# processor_beaglebone.net
KiCad netlist of a schematic drawn in Altium Designer
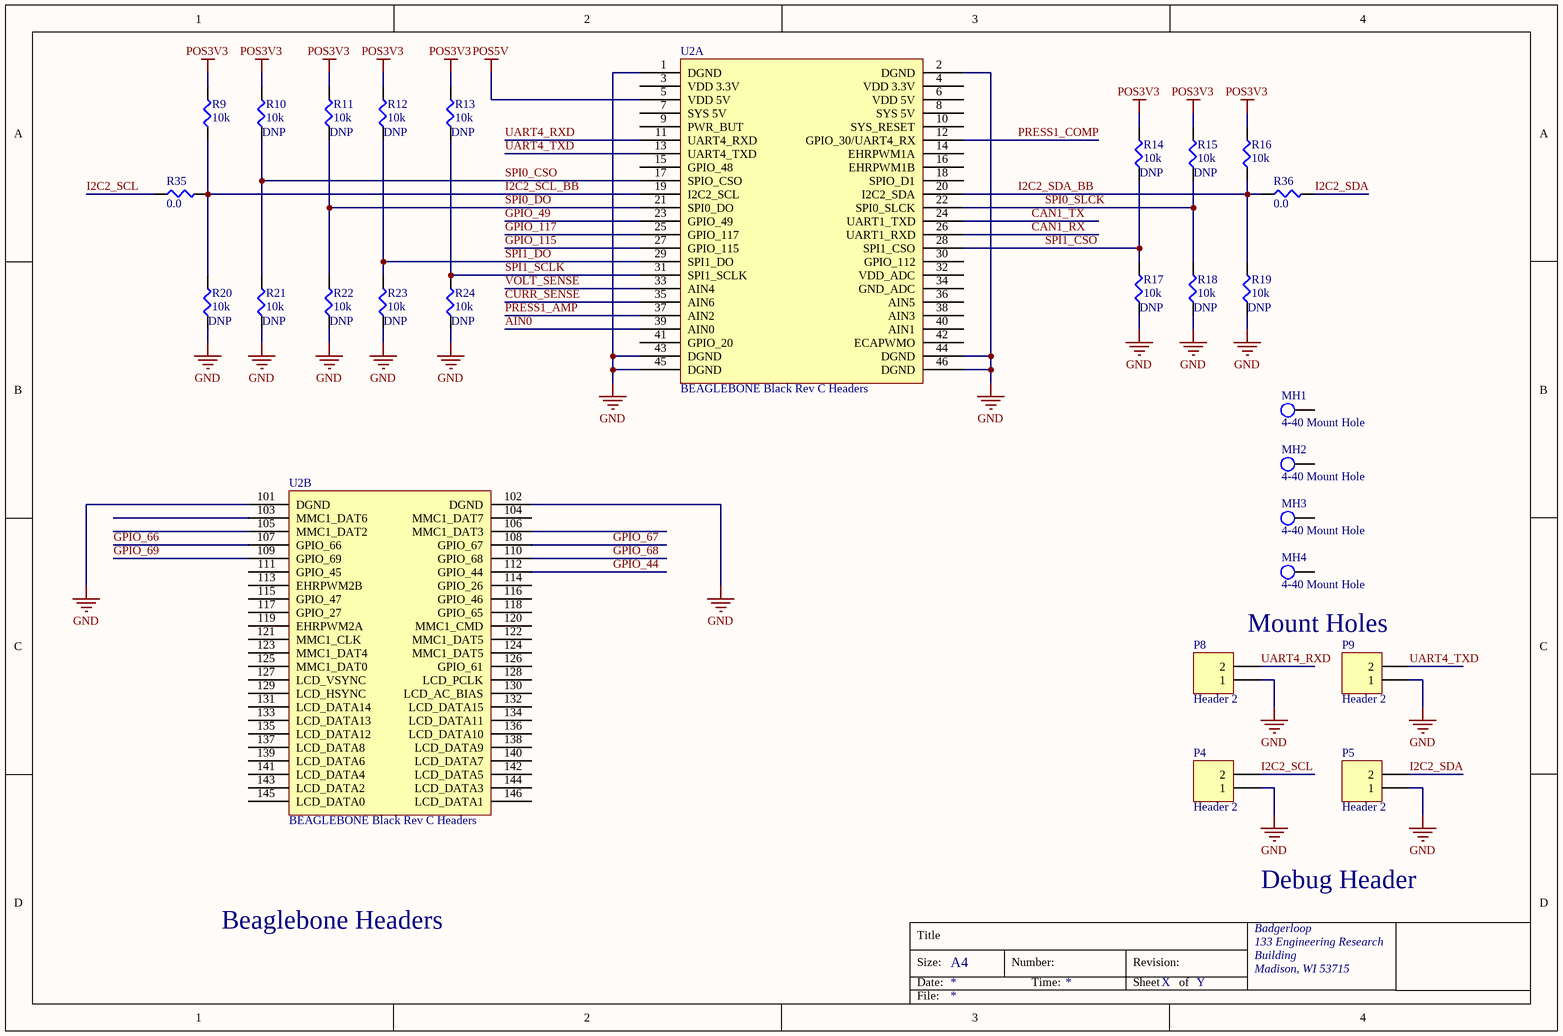
[diagram p0: processor_beaglebone.SchDoc]

(export (version "E")
  (design (tool "Eeschema 10.0.6"))
  (components
    (comp (ref "MH1")
      (value "4-40 Mount Hole")
      (footprint "MH")
      (libsource (lib "misc") (part "4-40 Mount Hole"))
    )
    (comp (ref "MH2")
      (value "4-40 Mount Hole")
      (footprint "MH")
      (libsource (lib "misc") (part "4-40 Mount Hole"))
    )
    (comp (ref "MH3")
      (value "4-40 Mount Hole")
      (footprint "MH")
      (libsource (lib "misc") (part "4-40 Mount Hole"))
    )
    (comp (ref "MH4")
      (value "4-40 Mount Hole")
      (footprint "MH")
      (libsource (lib "misc") (part "4-40 Mount Hole"))
    )
    (comp (ref "P4")
      (value "Header 2")
      (footprint "Pin Header 1x2 TH Pitch 2.54mm")
      (description "Header, 2-Pin")
      (fields (field (name "PUBLISHER") "Altium Limited"))
      (libsource (lib "connector") (part "Header 2"))
    )
    (comp (ref "P5")
      (value "Header 2")
      (footprint "Pin Header 1x2 TH Pitch 2.54mm")
      (description "Header, 2-Pin")
      (fields (field (name "PUBLISHER") "Altium Limited"))
      (libsource (lib "connector") (part "Header 2"))
    )
    (comp (ref "P8")
      (value "Header 2")
      (footprint "Pin Header 1x2 TH Pitch 2.54mm")
      (description "Header, 2-Pin")
      (fields (field (name "PUBLISHER") "Altium Limited"))
      (libsource (lib "connector") (part "Header 2"))
    )
    (comp (ref "P9")
      (value "Header 2")
      (footprint "Pin Header 1x2 TH Pitch 2.54mm")
      (description "Header, 2-Pin")
      (fields (field (name "PUBLISHER") "Altium Limited"))
      (libsource (lib "connector") (part "Header 2"))
    )
    (comp (ref "R9")
      (value "10k")
      (footprint "SMD-0402-RES")
      (description "RES SMD 10K OHM 5% 1/10W 0402")
      (fields (field (name "PART NUMBER") "ERJ-2GEJ103X") (field (name "DIGI-KEY PART NUMBER") "P10KJCT-ND"))
      (libsource (lib "resistor") (part "ERJ-2GEJ103X"))
    )
    (comp (ref "R10")
      (value "10k")
      (footprint "SMD-0402-RES")
      (description "RES SMD 10K OHM 5% 1/10W 0402")
      (fields
        (field (name "PART NUMBER") "ERJ-2GEJ103X")
        (field (name "DIGI-KEY PART NUMBER") "P10KJCT-ND")
        (field (name "DNP") "DNP")
      )
      (libsource (lib "resistor") (part "ERJ-2GEJ103X"))
    )
    (comp (ref "R11")
      (value "10k")
      (footprint "SMD-0402-RES")
      (description "RES SMD 10K OHM 5% 1/10W 0402")
      (fields
        (field (name "PART NUMBER") "ERJ-2GEJ103X")
        (field (name "DIGI-KEY PART NUMBER") "P10KJCT-ND")
        (field (name "DNP") "DNP")
      )
      (libsource (lib "resistor") (part "ERJ-2GEJ103X"))
    )
    (comp (ref "R12")
      (value "10k")
      (footprint "SMD-0402-RES")
      (description "RES SMD 10K OHM 5% 1/10W 0402")
      (fields
        (field (name "PART NUMBER") "ERJ-2GEJ103X")
        (field (name "DIGI-KEY PART NUMBER") "P10KJCT-ND")
        (field (name "DNP") "DNP")
      )
      (libsource (lib "resistor") (part "ERJ-2GEJ103X"))
    )
    (comp (ref "R13")
      (value "10k")
      (footprint "SMD-0402-RES")
      (description "RES SMD 10K OHM 5% 1/10W 0402")
      (fields
        (field (name "PART NUMBER") "ERJ-2GEJ103X")
        (field (name "DIGI-KEY PART NUMBER") "P10KJCT-ND")
        (field (name "DNP") "DNP")
      )
      (libsource (lib "resistor") (part "ERJ-2GEJ103X"))
    )
    (comp (ref "R14")
      (value "10k")
      (footprint "SMD-0402-RES")
      (description "RES SMD 10K OHM 5% 1/10W 0402")
      (fields
        (field (name "PART NUMBER") "ERJ-2GEJ103X")
        (field (name "DIGI-KEY PART NUMBER") "P10KJCT-ND")
        (field (name "DNP") "DNP")
      )
      (libsource (lib "resistor") (part "ERJ-2GEJ103X"))
    )
    (comp (ref "R15")
      (value "10k")
      (footprint "SMD-0402-RES")
      (description "RES SMD 10K OHM 5% 1/10W 0402")
      (fields
        (field (name "PART NUMBER") "ERJ-2GEJ103X")
        (field (name "DIGI-KEY PART NUMBER") "P10KJCT-ND")
        (field (name "DNP") "DNP")
      )
      (libsource (lib "resistor") (part "ERJ-2GEJ103X"))
    )
    (comp (ref "R16")
      (value "10k")
      (footprint "SMD-0402-RES")
      (description "RES SMD 10K OHM 5% 1/10W 0402")
      (fields (field (name "PART NUMBER") "ERJ-2GEJ103X") (field (name "DIGI-KEY PART NUMBER") "P10KJCT-ND"))
      (libsource (lib "resistor") (part "ERJ-2GEJ103X"))
    )
    (comp (ref "R17")
      (value "10k")
      (footprint "SMD-0402-RES")
      (description "RES SMD 10K OHM 5% 1/10W 0402")
      (fields
        (field (name "PART NUMBER") "ERJ-2GEJ103X")
        (field (name "DIGI-KEY PART NUMBER") "P10KJCT-ND")
        (field (name "DNP") "DNP")
      )
      (libsource (lib "resistor") (part "ERJ-2GEJ103X"))
    )
    (comp (ref "R18")
      (value "10k")
      (footprint "SMD-0402-RES")
      (description "RES SMD 10K OHM 5% 1/10W 0402")
      (fields
        (field (name "PART NUMBER") "ERJ-2GEJ103X")
        (field (name "DIGI-KEY PART NUMBER") "P10KJCT-ND")
        (field (name "DNP") "DNP")
      )
      (libsource (lib "resistor") (part "ERJ-2GEJ103X"))
    )
    (comp (ref "R19")
      (value "10k")
      (footprint "SMD-0402-RES")
      (description "RES SMD 10K OHM 5% 1/10W 0402")
      (fields
        (field (name "PART NUMBER") "ERJ-2GEJ103X")
        (field (name "DIGI-KEY PART NUMBER") "P10KJCT-ND")
        (field (name "DNP") "DNP")
      )
      (libsource (lib "resistor") (part "ERJ-2GEJ103X"))
    )
    (comp (ref "R20")
      (value "10k")
      (footprint "SMD-0402-RES")
      (description "RES SMD 10K OHM 5% 1/10W 0402")
      (fields
        (field (name "PART NUMBER") "ERJ-2GEJ103X")
        (field (name "DIGI-KEY PART NUMBER") "P10KJCT-ND")
        (field (name "DNP") "DNP")
      )
      (libsource (lib "resistor") (part "ERJ-2GEJ103X"))
    )
    (comp (ref "R21")
      (value "10k")
      (footprint "SMD-0402-RES")
      (description "RES SMD 10K OHM 5% 1/10W 0402")
      (fields
        (field (name "PART NUMBER") "ERJ-2GEJ103X")
        (field (name "DIGI-KEY PART NUMBER") "P10KJCT-ND")
        (field (name "DNP") "DNP")
      )
      (libsource (lib "resistor") (part "ERJ-2GEJ103X"))
    )
    (comp (ref "R22")
      (value "10k")
      (footprint "SMD-0402-RES")
      (description "RES SMD 10K OHM 5% 1/10W 0402")
      (fields
        (field (name "PART NUMBER") "ERJ-2GEJ103X")
        (field (name "DIGI-KEY PART NUMBER") "P10KJCT-ND")
        (field (name "DNP") "DNP")
      )
      (libsource (lib "resistor") (part "ERJ-2GEJ103X"))
    )
    (comp (ref "R23")
      (value "10k")
      (footprint "SMD-0402-RES")
      (description "RES SMD 10K OHM 5% 1/10W 0402")
      (fields
        (field (name "PART NUMBER") "ERJ-2GEJ103X")
        (field (name "DIGI-KEY PART NUMBER") "P10KJCT-ND")
        (field (name "DNP") "DNP")
      )
      (libsource (lib "resistor") (part "ERJ-2GEJ103X"))
    )
    (comp (ref "R24")
      (value "10k")
      (footprint "SMD-0402-RES")
      (description "RES SMD 10K OHM 5% 1/10W 0402")
      (fields
        (field (name "PART NUMBER") "ERJ-2GEJ103X")
        (field (name "DIGI-KEY PART NUMBER") "P10KJCT-ND")
        (field (name "DNP") "DNP")
      )
      (libsource (lib "resistor") (part "ERJ-2GEJ103X"))
    )
    (comp (ref "R35")
      (value "0.0")
      (footprint "SMD-0402-RES")
      (description "RES SMD 0.0OHM JUMPER 1/10W 0402")
      (fields (field (name "PART NUMBER") "ERJ-2GE0R00X") (field (name "DIGI-KEY PART NUMBER") "P0.0JCT-ND"))
      (libsource (lib "resistor") (part "ERJ-2GE0R00X"))
    )
    (comp (ref "R36")
      (value "0.0")
      (footprint "SMD-0402-RES")
      (description "RES SMD 0.0OHM JUMPER 1/10W 0402")
      (fields (field (name "PART NUMBER") "ERJ-2GE0R00X") (field (name "DIGI-KEY PART NUMBER") "P0.0JCT-ND"))
      (libsource (lib "resistor") (part "ERJ-2GE0R00X"))
    )
    (comp (ref "U2")
      (value "BEAGLEBONE Black Rev C Headers")
      (footprint "Beaglebone_Topside")
      (description "Beaglebone Black Rev C Header")
      (libsource (lib "temp") (part "Beaglebone"))
    )
  )
  (nets
    (net (code "1") (name "/AIN0") (class "Default")
      (node (ref "U2") (pin "39") (pinfunction "AIN0_39") (pintype "passive"))
    )
    (net (code "2") (name "/CAN1_RX") (class "Default")
      (node (ref "U2") (pin "26") (pinfunction "UART1_RXD_26") (pintype "passive"))
    )
    (net (code "3") (name "/CAN1_TX") (class "Default")
      (node (ref "U2") (pin "24") (pinfunction "UART1_TXD_24") (pintype "passive"))
    )
    (net (code "4") (name "/CURR_SENSE") (class "Default")
      (node (ref "U2") (pin "35") (pinfunction "AIN6_35") (pintype "passive"))
    )
    (net (code "5") (name "/GPIO_44") (class "Default")
      (node (ref "U2") (pin "112") (pinfunction "GPIO_44_112") (pintype "passive"))
    )
    (net (code "6") (name "/GPIO_49") (class "Default")
      (node (ref "U2") (pin "23") (pinfunction "GPIO_49_23") (pintype "passive"))
    )
    (net (code "7") (name "/GPIO_66") (class "Default")
      (node (ref "U2") (pin "107") (pinfunction "GPIO_66_107") (pintype "passive"))
    )
    (net (code "8") (name "/GPIO_67") (class "Default")
      (node (ref "U2") (pin "108") (pinfunction "GPIO_67_108") (pintype "passive"))
    )
    (net (code "9") (name "/GPIO_68") (class "Default")
      (node (ref "U2") (pin "110") (pinfunction "GPIO_68_110") (pintype "passive"))
    )
    (net (code "10") (name "/GPIO_69") (class "Default")
      (node (ref "U2") (pin "109") (pinfunction "GPIO_69_109") (pintype "passive"))
    )
    (net (code "11") (name "/GPIO_115") (class "Default")
      (node (ref "U2") (pin "27") (pinfunction "GPIO_115_27") (pintype "passive"))
    )
    (net (code "12") (name "/GPIO_117") (class "Default")
      (node (ref "U2") (pin "25") (pinfunction "GPIO_117_25") (pintype "passive"))
    )
    (net (code "13") (name "/I2C2_SCL") (class "Default")
      (node (ref "P4") (pin "2") (pinfunction "2_2") (pintype "passive"))
      (node (ref "R35") (pin "1") (pinfunction "1_1") (pintype "passive"))
    )
    (net (code "14") (name "/I2C2_SCL_BB") (class "Default")
      (node (ref "R20") (pin "2") (pinfunction "2_2") (pintype "passive"))
      (node (ref "R35") (pin "2") (pinfunction "2_2") (pintype "passive"))
      (node (ref "R9") (pin "1") (pinfunction "1_1") (pintype "passive"))
      (node (ref "U2") (pin "19") (pinfunction "I2C2_SCL_19") (pintype "passive"))
    )
    (net (code "15") (name "/I2C2_SDA") (class "Default")
      (node (ref "P5") (pin "2") (pinfunction "2_2") (pintype "passive"))
      (node (ref "R36") (pin "2") (pinfunction "2_2") (pintype "passive"))
    )
    (net (code "16") (name "/I2C2_SDA_BB") (class "Default")
      (node (ref "R16") (pin "1") (pinfunction "1_1") (pintype "passive"))
      (node (ref "R19") (pin "2") (pinfunction "2_2") (pintype "passive"))
      (node (ref "R36") (pin "1") (pinfunction "1_1") (pintype "passive"))
      (node (ref "U2") (pin "20") (pinfunction "I2C2_SDA_20") (pintype "passive"))
    )
    (net (code "17") (name "/PRESS1_AMP") (class "Default")
      (node (ref "U2") (pin "37") (pinfunction "AIN2_37") (pintype "passive"))
    )
    (net (code "18") (name "/PRESS1_COMP") (class "Default")
      (node (ref "U2") (pin "12") (pinfunction "GPIO_30/UART4_RX_12") (pintype "passive"))
    )
    (net (code "19") (name "/SPI0_CSO") (class "Default")
      (node (ref "R10") (pin "1") (pinfunction "1_1") (pintype "passive"))
      (node (ref "R21") (pin "2") (pinfunction "2_2") (pintype "passive"))
      (node (ref "U2") (pin "17") (pinfunction "SPIO_CSO_17") (pintype "passive"))
    )
    (net (code "20") (name "/SPI0_DO") (class "Default")
      (node (ref "R11") (pin "1") (pinfunction "1_1") (pintype "passive"))
      (node (ref "R22") (pin "2") (pinfunction "2_2") (pintype "passive"))
      (node (ref "U2") (pin "21") (pinfunction "SPI0_DO_21") (pintype "passive"))
    )
    (net (code "21") (name "/SPI0_SLCK") (class "Default")
      (node (ref "R15") (pin "1") (pinfunction "1_1") (pintype "passive"))
      (node (ref "R18") (pin "2") (pinfunction "2_2") (pintype "passive"))
      (node (ref "U2") (pin "22") (pinfunction "SPI0_SLCK_22") (pintype "passive"))
    )
    (net (code "22") (name "/SPI1_CSO") (class "Default")
      (node (ref "R14") (pin "1") (pinfunction "1_1") (pintype "passive"))
      (node (ref "R17") (pin "2") (pinfunction "2_2") (pintype "passive"))
      (node (ref "U2") (pin "28") (pinfunction "SPI1_CSO_28") (pintype "passive"))
    )
    (net (code "23") (name "/SPI1_DO") (class "Default")
      (node (ref "R12") (pin "1") (pinfunction "1_1") (pintype "passive"))
      (node (ref "R23") (pin "2") (pinfunction "2_2") (pintype "passive"))
      (node (ref "U2") (pin "29") (pinfunction "SPI1_DO_29") (pintype "passive"))
    )
    (net (code "24") (name "/SPI1_SCLK") (class "Default")
      (node (ref "R13") (pin "1") (pinfunction "1_1") (pintype "passive"))
      (node (ref "R24") (pin "2") (pinfunction "2_2") (pintype "passive"))
      (node (ref "U2") (pin "31") (pinfunction "SPI1_SCLK_31") (pintype "passive"))
    )
    (net (code "25") (name "/UART4_RXD") (class "Default")
      (node (ref "P8") (pin "2") (pinfunction "2_2") (pintype "passive"))
      (node (ref "U2") (pin "11") (pinfunction "UART4_RXD_11") (pintype "passive"))
    )
    (net (code "26") (name "/UART4_TXD") (class "Default")
      (node (ref "P9") (pin "2") (pinfunction "2_2") (pintype "passive"))
      (node (ref "U2") (pin "13") (pinfunction "UART4_TXD_13") (pintype "passive"))
    )
    (net (code "27") (name "/VOLT_SENSE") (class "Default")
      (node (ref "U2") (pin "33") (pinfunction "AIN4_33") (pintype "passive"))
    )
    (net (code "28") (name "GND") (class "Default")
      (node (ref "P4") (pin "1") (pinfunction "1_1") (pintype "passive"))
      (node (ref "P5") (pin "1") (pinfunction "1_1") (pintype "passive"))
      (node (ref "P8") (pin "1") (pinfunction "1_1") (pintype "passive"))
      (node (ref "P9") (pin "1") (pinfunction "1_1") (pintype "passive"))
      (node (ref "R17") (pin "1") (pinfunction "1_1") (pintype "passive"))
      (node (ref "R18") (pin "1") (pinfunction "1_1") (pintype "passive"))
      (node (ref "R19") (pin "1") (pinfunction "1_1") (pintype "passive"))
      (node (ref "R20") (pin "1") (pinfunction "1_1") (pintype "passive"))
      (node (ref "R21") (pin "1") (pinfunction "1_1") (pintype "passive"))
      (node (ref "R22") (pin "1") (pinfunction "1_1") (pintype "passive"))
      (node (ref "R23") (pin "1") (pinfunction "1_1") (pintype "passive"))
      (node (ref "R24") (pin "1") (pinfunction "1_1") (pintype "passive"))
      (node (ref "U2") (pin "1") (pinfunction "DGND_1") (pintype "passive"))
      (node (ref "U2") (pin "101") (pinfunction "DGND_101") (pintype "passive"))
      (node (ref "U2") (pin "102") (pinfunction "DGND_102") (pintype "passive"))
      (node (ref "U2") (pin "2") (pinfunction "DGND_2") (pintype "passive"))
      (node (ref "U2") (pin "43") (pinfunction "DGND_43") (pintype "passive"))
      (node (ref "U2") (pin "44") (pinfunction "DGND_44") (pintype "passive"))
      (node (ref "U2") (pin "45") (pinfunction "DGND_45") (pintype "passive"))
      (node (ref "U2") (pin "46") (pinfunction "DGND_46") (pintype "passive"))
    )
    (net (code "29") (name "POS3V3") (class "Default")
      (node (ref "R10") (pin "2") (pinfunction "2_2") (pintype "passive"))
      (node (ref "R11") (pin "2") (pinfunction "2_2") (pintype "passive"))
      (node (ref "R12") (pin "2") (pinfunction "2_2") (pintype "passive"))
      (node (ref "R13") (pin "2") (pinfunction "2_2") (pintype "passive"))
      (node (ref "R14") (pin "2") (pinfunction "2_2") (pintype "passive"))
      (node (ref "R15") (pin "2") (pinfunction "2_2") (pintype "passive"))
      (node (ref "R16") (pin "2") (pinfunction "2_2") (pintype "passive"))
      (node (ref "R9") (pin "2") (pinfunction "2_2") (pintype "passive"))
    )
    (net (code "30") (name "POS5V") (class "Default")
      (node (ref "U2") (pin "5") (pinfunction "VDD_5V_5") (pintype "passive"))
    )
    (net (code "31") (name "unconnected-(MH1-Pad46)") (class "Default")
      (node (ref "MH1") (pin "46") (pinfunction "46_46") (pintype "passive"))
    )
    (net (code "32") (name "unconnected-(MH2-Pad46)") (class "Default")
      (node (ref "MH2") (pin "46") (pinfunction "46_46") (pintype "passive"))
    )
    (net (code "33") (name "unconnected-(MH3-Pad46)") (class "Default")
      (node (ref "MH3") (pin "46") (pinfunction "46_46") (pintype "passive"))
    )
    (net (code "34") (name "unconnected-(MH4-Pad46)") (class "Default")
      (node (ref "MH4") (pin "46") (pinfunction "46_46") (pintype "passive"))
    )
    (net (code "35") (name "unconnected-(U2A-AIN1-Pad40)") (class "Default")
      (node (ref "U2") (pin "40") (pinfunction "AIN1_40") (pintype "passive"))
    )
    (net (code "36") (name "unconnected-(U2A-AIN3-Pad38)") (class "Default")
      (node (ref "U2") (pin "38") (pinfunction "AIN3_38") (pintype "passive"))
    )
    (net (code "37") (name "unconnected-(U2A-AIN5-Pad36)") (class "Default")
      (node (ref "U2") (pin "36") (pinfunction "AIN5_36") (pintype "passive"))
    )
    (net (code "38") (name "unconnected-(U2A-ECAPWMO-Pad42)") (class "Default")
      (node (ref "U2") (pin "42") (pinfunction "ECAPWMO_42") (pintype "passive"))
    )
    (net (code "39") (name "unconnected-(U2A-EHRPWM1A-Pad14)") (class "Default")
      (node (ref "U2") (pin "14") (pinfunction "EHRPWM1A_14") (pintype "passive"))
    )
    (net (code "40") (name "unconnected-(U2A-EHRPWM1B-Pad16)") (class "Default")
      (node (ref "U2") (pin "16") (pinfunction "EHRPWM1B_16") (pintype "passive"))
    )
    (net (code "41") (name "unconnected-(U2A-GND_ADC-Pad34)") (class "Default")
      (node (ref "U2") (pin "34") (pinfunction "GND_ADC_34") (pintype "passive"))
    )
    (net (code "42") (name "unconnected-(U2A-GPIO_20-Pad41)") (class "Default")
      (node (ref "U2") (pin "41") (pinfunction "GPIO_20_41") (pintype "passive"))
    )
    (net (code "43") (name "unconnected-(U2A-GPIO_48-Pad15)") (class "Default")
      (node (ref "U2") (pin "15") (pinfunction "GPIO_48_15") (pintype "passive"))
    )
    (net (code "44") (name "unconnected-(U2A-GPIO_112-Pad30)") (class "Default")
      (node (ref "U2") (pin "30") (pinfunction "GPIO_112_30") (pintype "passive"))
    )
    (net (code "45") (name "unconnected-(U2A-PWR_BUT-Pad9)") (class "Default")
      (node (ref "U2") (pin "9") (pinfunction "PWR_BUT_9") (pintype "passive"))
    )
    (net (code "46") (name "unconnected-(U2A-SPIO_D1-Pad18)") (class "Default")
      (node (ref "U2") (pin "18") (pinfunction "SPIO_D1_18") (pintype "passive"))
    )
    (net (code "47") (name "unconnected-(U2A-SYS_5V-Pad7)") (class "Default")
      (node (ref "U2") (pin "7") (pinfunction "SYS_5V_7") (pintype "passive"))
    )
    (net (code "48") (name "unconnected-(U2A-SYS_5V-Pad8)") (class "Default")
      (node (ref "U2") (pin "8") (pinfunction "SYS_5V_8") (pintype "passive"))
    )
    (net (code "49") (name "unconnected-(U2A-SYS_RESET-Pad10)") (class "Default")
      (node (ref "U2") (pin "10") (pinfunction "SYS_RESET_10") (pintype "passive"))
    )
    (net (code "50") (name "unconnected-(U2A-VDD_3.3V-Pad3)") (class "Default")
      (node (ref "U2") (pin "3") (pinfunction "VDD_3.3V_3") (pintype "passive"))
    )
    (net (code "51") (name "unconnected-(U2A-VDD_3.3V-Pad4)") (class "Default")
      (node (ref "U2") (pin "4") (pinfunction "VDD_3.3V_4") (pintype "passive"))
    )
    (net (code "52") (name "unconnected-(U2A-VDD_5V-Pad6)") (class "Default")
      (node (ref "U2") (pin "6") (pinfunction "VDD_5V_6") (pintype "passive"))
    )
    (net (code "53") (name "unconnected-(U2A-VDD_ADC-Pad32)") (class "Default")
      (node (ref "U2") (pin "32") (pinfunction "VDD_ADC_32") (pintype "passive"))
    )
    (net (code "54") (name "unconnected-(U2B-EHRPWM2A-Pad119)") (class "Default")
      (node (ref "U2") (pin "119") (pinfunction "EHRPWM2A_119") (pintype "passive"))
    )
    (net (code "55") (name "unconnected-(U2B-EHRPWM2B-Pad113)") (class "Default")
      (node (ref "U2") (pin "113") (pinfunction "EHRPWM2B_113") (pintype "passive"))
    )
    (net (code "56") (name "unconnected-(U2B-GPIO_26-Pad114)") (class "Default")
      (node (ref "U2") (pin "114") (pinfunction "GPIO_26_114") (pintype "passive"))
    )
    (net (code "57") (name "unconnected-(U2B-GPIO_27-Pad117)") (class "Default")
      (node (ref "U2") (pin "117") (pinfunction "GPIO_27_117") (pintype "passive"))
    )
    (net (code "58") (name "unconnected-(U2B-GPIO_45-Pad111)") (class "Default")
      (node (ref "U2") (pin "111") (pinfunction "GPIO_45_111") (pintype "passive"))
    )
    (net (code "59") (name "unconnected-(U2B-GPIO_46-Pad116)") (class "Default")
      (node (ref "U2") (pin "116") (pinfunction "GPIO_46_116") (pintype "passive"))
    )
    (net (code "60") (name "unconnected-(U2B-GPIO_47-Pad115)") (class "Default")
      (node (ref "U2") (pin "115") (pinfunction "GPIO_47_115") (pintype "passive"))
    )
    (net (code "61") (name "unconnected-(U2B-GPIO_61-Pad126)") (class "Default")
      (node (ref "U2") (pin "126") (pinfunction "GPIO_61_126") (pintype "passive"))
    )
    (net (code "62") (name "unconnected-(U2B-GPIO_65-Pad118)") (class "Default")
      (node (ref "U2") (pin "118") (pinfunction "GPIO_65_118") (pintype "passive"))
    )
    (net (code "63") (name "unconnected-(U2B-LCD_AC_BIAS-Pad130)") (class "Default")
      (node (ref "U2") (pin "130") (pinfunction "LCD_AC_BIAS_130") (pintype "passive"))
    )
    (net (code "64") (name "unconnected-(U2B-LCD_DATA0-Pad145)") (class "Default")
      (node (ref "U2") (pin "145") (pinfunction "LCD_DATA0_145") (pintype "passive"))
    )
    (net (code "65") (name "unconnected-(U2B-LCD_DATA1-Pad146)") (class "Default")
      (node (ref "U2") (pin "146") (pinfunction "LCD_DATA1_146") (pintype "passive"))
    )
    (net (code "66") (name "unconnected-(U2B-LCD_DATA2-Pad143)") (class "Default")
      (node (ref "U2") (pin "143") (pinfunction "LCD_DATA2_143") (pintype "passive"))
    )
    (net (code "67") (name "unconnected-(U2B-LCD_DATA3-Pad144)") (class "Default")
      (node (ref "U2") (pin "144") (pinfunction "LCD_DATA3_144") (pintype "passive"))
    )
    (net (code "68") (name "unconnected-(U2B-LCD_DATA4-Pad141)") (class "Default")
      (node (ref "U2") (pin "141") (pinfunction "LCD_DATA4_141") (pintype "passive"))
    )
    (net (code "69") (name "unconnected-(U2B-LCD_DATA5-Pad142)") (class "Default")
      (node (ref "U2") (pin "142") (pinfunction "LCD_DATA5_142") (pintype "passive"))
    )
    (net (code "70") (name "unconnected-(U2B-LCD_DATA6-Pad139)") (class "Default")
      (node (ref "U2") (pin "139") (pinfunction "LCD_DATA6_139") (pintype "passive"))
    )
    (net (code "71") (name "unconnected-(U2B-LCD_DATA7-Pad140)") (class "Default")
      (node (ref "U2") (pin "140") (pinfunction "LCD_DATA7_140") (pintype "passive"))
    )
    (net (code "72") (name "unconnected-(U2B-LCD_DATA8-Pad137)") (class "Default")
      (node (ref "U2") (pin "137") (pinfunction "LCD_DATA8_137") (pintype "passive"))
    )
    (net (code "73") (name "unconnected-(U2B-LCD_DATA9-Pad138)") (class "Default")
      (node (ref "U2") (pin "138") (pinfunction "LCD_DATA9_138") (pintype "passive"))
    )
    (net (code "74") (name "unconnected-(U2B-LCD_DATA10-Pad136)") (class "Default")
      (node (ref "U2") (pin "136") (pinfunction "LCD_DATA10_136") (pintype "passive"))
    )
    (net (code "75") (name "unconnected-(U2B-LCD_DATA11-Pad134)") (class "Default")
      (node (ref "U2") (pin "134") (pinfunction "LCD_DATA11_134") (pintype "passive"))
    )
    (net (code "76") (name "unconnected-(U2B-LCD_DATA12-Pad135)") (class "Default")
      (node (ref "U2") (pin "135") (pinfunction "LCD_DATA12_135") (pintype "passive"))
    )
    (net (code "77") (name "unconnected-(U2B-LCD_DATA13-Pad133)") (class "Default")
      (node (ref "U2") (pin "133") (pinfunction "LCD_DATA13_133") (pintype "passive"))
    )
    (net (code "78") (name "unconnected-(U2B-LCD_DATA14-Pad131)") (class "Default")
      (node (ref "U2") (pin "131") (pinfunction "LCD_DATA14_131") (pintype "passive"))
    )
    (net (code "79") (name "unconnected-(U2B-LCD_DATA15-Pad132)") (class "Default")
      (node (ref "U2") (pin "132") (pinfunction "LCD_DATA15_132") (pintype "passive"))
    )
    (net (code "80") (name "unconnected-(U2B-LCD_HSYNC-Pad129)") (class "Default")
      (node (ref "U2") (pin "129") (pinfunction "LCD_HSYNC_129") (pintype "passive"))
    )
    (net (code "81") (name "unconnected-(U2B-LCD_PCLK-Pad128)") (class "Default")
      (node (ref "U2") (pin "128") (pinfunction "LCD_PCLK_128") (pintype "passive"))
    )
    (net (code "82") (name "unconnected-(U2B-LCD_VSYNC-Pad127)") (class "Default")
      (node (ref "U2") (pin "127") (pinfunction "LCD_VSYNC_127") (pintype "passive"))
    )
    (net (code "83") (name "unconnected-(U2B-MMC1_CLK-Pad121)") (class "Default")
      (node (ref "U2") (pin "121") (pinfunction "MMC1_CLK_121") (pintype "passive"))
    )
    (net (code "84") (name "unconnected-(U2B-MMC1_CMD-Pad120)") (class "Default")
      (node (ref "U2") (pin "120") (pinfunction "MMC1_CMD_120") (pintype "passive"))
    )
    (net (code "85") (name "unconnected-(U2B-MMC1_DAT0-Pad125)") (class "Default")
      (node (ref "U2") (pin "125") (pinfunction "MMC1_DAT0_125") (pintype "passive"))
    )
    (net (code "86") (name "unconnected-(U2B-MMC1_DAT2-Pad105)") (class "Default")
      (node (ref "U2") (pin "105") (pinfunction "MMC1_DAT2_105") (pintype "passive"))
    )
    (net (code "87") (name "unconnected-(U2B-MMC1_DAT3-Pad106)") (class "Default")
      (node (ref "U2") (pin "106") (pinfunction "MMC1_DAT3_106") (pintype "passive"))
    )
    (net (code "88") (name "unconnected-(U2B-MMC1_DAT4-Pad123)") (class "Default")
      (node (ref "U2") (pin "123") (pinfunction "MMC1_DAT4_123") (pintype "passive"))
    )
    (net (code "89") (name "unconnected-(U2B-MMC1_DAT5-Pad122)") (class "Default")
      (node (ref "U2") (pin "122") (pinfunction "MMC1_DAT5_122") (pintype "passive"))
    )
    (net (code "90") (name "unconnected-(U2B-MMC1_DAT5-Pad124)") (class "Default")
      (node (ref "U2") (pin "124") (pinfunction "MMC1_DAT5_124") (pintype "passive"))
    )
    (net (code "91") (name "unconnected-(U2B-MMC1_DAT6-Pad103)") (class "Default")
      (node (ref "U2") (pin "103") (pinfunction "MMC1_DAT6_103") (pintype "passive"))
    )
    (net (code "92") (name "unconnected-(U2B-MMC1_DAT7-Pad104)") (class "Default")
      (node (ref "U2") (pin "104") (pinfunction "MMC1_DAT7_104") (pintype "passive"))
    )
  )
)
